# Project_datacommunicatie.net
KiCad netlist of a schematic drawn in EAGLE
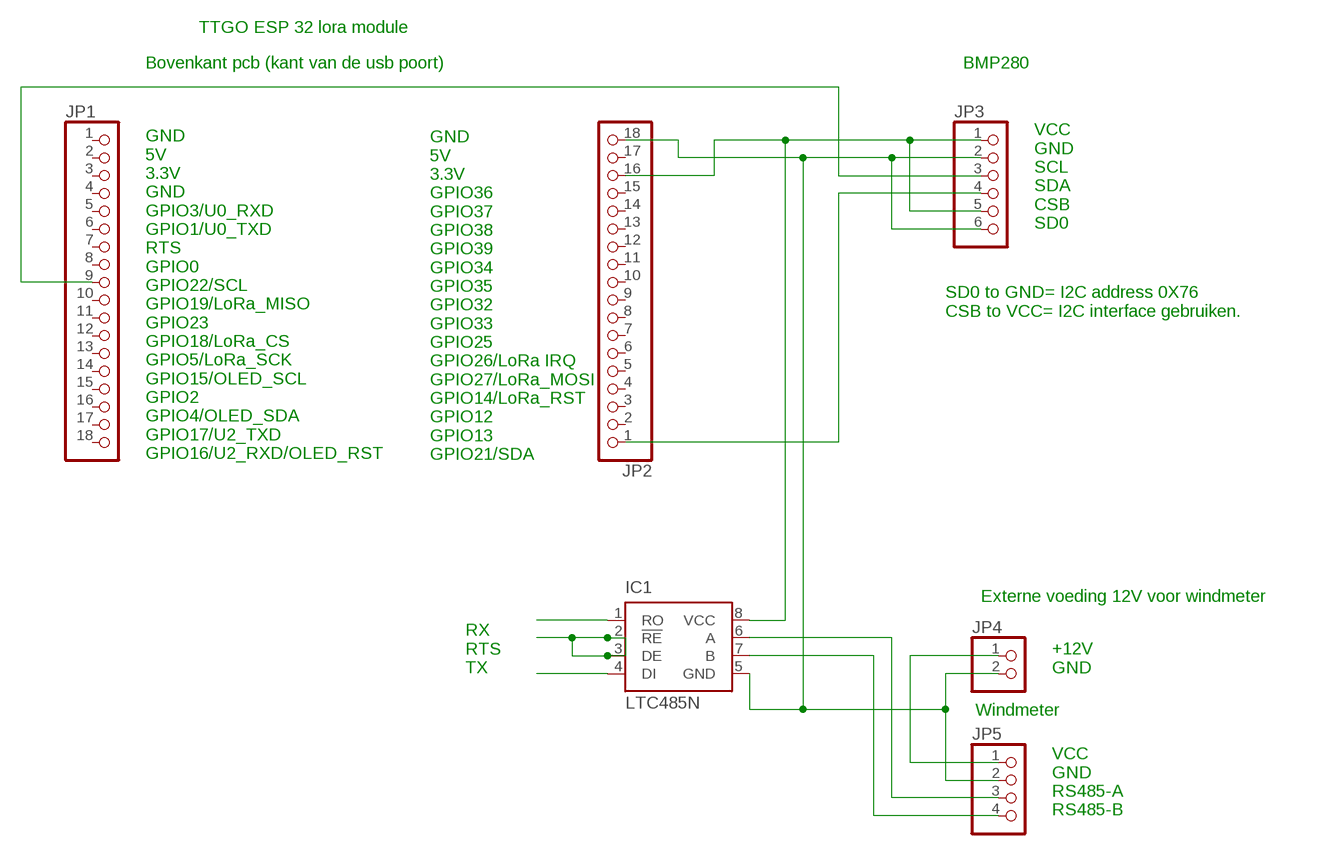
[diagram p0: schematic, sheet 1]

(export (version "E")
  (design (tool "Eeschema 10.0.6"))
  (components
    (comp (ref "IC1")
      (value "LTC485N")
      (footprint "eagle-import:DIL08")
      (libsource (lib "eagle-import") (part "LTC485N"))
    )
    (comp (ref "JP1")
      (value "PINHD-1X18")
      (footprint "eagle-import:1X18")
      (libsource (lib "eagle-import") (part "PINHD-1X18"))
    )
    (comp (ref "JP2")
      (value "PINHD-1X18")
      (footprint "eagle-import:1X18")
      (libsource (lib "eagle-import") (part "PINHD-1X18"))
    )
    (comp (ref "JP3")
      (value "PINHD-1X6")
      (footprint "eagle-import:1X06")
      (libsource (lib "eagle-import") (part "PINHD-1X6"))
    )
    (comp (ref "JP4")
      (value "PINHD-1X2")
      (footprint "eagle-import:1X02")
      (libsource (lib "eagle-import") (part "PINHD-1X2"))
    )
    (comp (ref "JP5")
      (value "PINHD-1X4")
      (footprint "eagle-import:1X04")
      (libsource (lib "eagle-import") (part "PINHD-1X4"))
    )
  )
  (nets
    (net (code "1") (name "Net-(IC1-A)") (class "Default")
      (node (ref "IC1") (pin "6") (pinfunction "A_6") (pintype "bidirectional"))
      (node (ref "JP5") (pin "3") (pinfunction "3_3") (pintype "passive"))
    )
    (net (code "2") (name "Net-(IC1-B)") (class "Default")
      (node (ref "IC1") (pin "7") (pinfunction "B_7") (pintype "bidirectional"))
      (node (ref "JP5") (pin "4") (pinfunction "4_4") (pintype "passive"))
    )
    (net (code "3") (name "Net-(IC1-DE)") (class "Default")
      (node (ref "IC1") (pin "2") (pinfunction "~{RE}_2") (pintype "input"))
      (node (ref "IC1") (pin "3") (pinfunction "DE_3") (pintype "input"))
    )
    (net (code "4") (name "Net-(IC1-GND)") (class "Default")
      (node (ref "IC1") (pin "5") (pinfunction "GND_5") (pintype "input"))
      (node (ref "JP2") (pin "18") (pinfunction "18_18") (pintype "passive"))
      (node (ref "JP3") (pin "2") (pinfunction "2_2") (pintype "passive"))
      (node (ref "JP3") (pin "6") (pinfunction "6_6") (pintype "passive"))
      (node (ref "JP4") (pin "2") (pinfunction "2_2") (pintype "passive"))
      (node (ref "JP5") (pin "2") (pinfunction "2_2") (pintype "passive"))
    )
    (net (code "5") (name "Net-(IC1-VCC)") (class "Default")
      (node (ref "IC1") (pin "8") (pinfunction "VCC_8") (pintype "input"))
      (node (ref "JP2") (pin "16") (pinfunction "16_16") (pintype "passive"))
      (node (ref "JP3") (pin "1") (pinfunction "1_1") (pintype "passive"))
      (node (ref "JP3") (pin "5") (pinfunction "5_5") (pintype "passive"))
    )
    (net (code "6") (name "Net-(JP1-Pad9)") (class "Default")
      (node (ref "JP1") (pin "9") (pinfunction "9_9") (pintype "passive"))
      (node (ref "JP3") (pin "3") (pinfunction "3_3") (pintype "passive"))
    )
    (net (code "7") (name "Net-(JP2-Pad1)") (class "Default")
      (node (ref "JP2") (pin "1") (pinfunction "1_1") (pintype "passive"))
      (node (ref "JP3") (pin "4") (pinfunction "4_4") (pintype "passive"))
    )
    (net (code "8") (name "Net-(JP4-Pad1)") (class "Default")
      (node (ref "JP4") (pin "1") (pinfunction "1_1") (pintype "passive"))
      (node (ref "JP5") (pin "1") (pinfunction "1_1") (pintype "passive"))
    )
    (net (code "9") (name "unconnected-(IC1-DI-Pad4)") (class "Default")
      (node (ref "IC1") (pin "4") (pinfunction "DI_4") (pintype "input"))
    )
    (net (code "10") (name "unconnected-(IC1-RO-Pad1)") (class "Default")
      (node (ref "IC1") (pin "1") (pinfunction "RO_1") (pintype "output"))
    )
    (net (code "11") (name "unconnected-(JP1-Pad1)") (class "Default")
      (node (ref "JP1") (pin "1") (pinfunction "1_1") (pintype "passive"))
    )
    (net (code "12") (name "unconnected-(JP1-Pad2)") (class "Default")
      (node (ref "JP1") (pin "2") (pinfunction "2_2") (pintype "passive"))
    )
    (net (code "13") (name "unconnected-(JP1-Pad3)") (class "Default")
      (node (ref "JP1") (pin "3") (pinfunction "3_3") (pintype "passive"))
    )
    (net (code "14") (name "unconnected-(JP1-Pad4)") (class "Default")
      (node (ref "JP1") (pin "4") (pinfunction "4_4") (pintype "passive"))
    )
    (net (code "15") (name "unconnected-(JP1-Pad5)") (class "Default")
      (node (ref "JP1") (pin "5") (pinfunction "5_5") (pintype "passive"))
    )
    (net (code "16") (name "unconnected-(JP1-Pad6)") (class "Default")
      (node (ref "JP1") (pin "6") (pinfunction "6_6") (pintype "passive"))
    )
    (net (code "17") (name "unconnected-(JP1-Pad7)") (class "Default")
      (node (ref "JP1") (pin "7") (pinfunction "7_7") (pintype "passive"))
    )
    (net (code "18") (name "unconnected-(JP1-Pad8)") (class "Default")
      (node (ref "JP1") (pin "8") (pinfunction "8_8") (pintype "passive"))
    )
    (net (code "19") (name "unconnected-(JP1-Pad10)") (class "Default")
      (node (ref "JP1") (pin "10") (pinfunction "10_10") (pintype "passive"))
    )
    (net (code "20") (name "unconnected-(JP1-Pad11)") (class "Default")
      (node (ref "JP1") (pin "11") (pinfunction "11_11") (pintype "passive"))
    )
    (net (code "21") (name "unconnected-(JP1-Pad12)") (class "Default")
      (node (ref "JP1") (pin "12") (pinfunction "12_12") (pintype "passive"))
    )
    (net (code "22") (name "unconnected-(JP1-Pad13)") (class "Default")
      (node (ref "JP1") (pin "13") (pinfunction "13_13") (pintype "passive"))
    )
    (net (code "23") (name "unconnected-(JP1-Pad14)") (class "Default")
      (node (ref "JP1") (pin "14") (pinfunction "14_14") (pintype "passive"))
    )
    (net (code "24") (name "unconnected-(JP1-Pad15)") (class "Default")
      (node (ref "JP1") (pin "15") (pinfunction "15_15") (pintype "passive"))
    )
    (net (code "25") (name "unconnected-(JP1-Pad16)") (class "Default")
      (node (ref "JP1") (pin "16") (pinfunction "16_16") (pintype "passive"))
    )
    (net (code "26") (name "unconnected-(JP1-Pad17)") (class "Default")
      (node (ref "JP1") (pin "17") (pinfunction "17_17") (pintype "passive"))
    )
    (net (code "27") (name "unconnected-(JP1-Pad18)") (class "Default")
      (node (ref "JP1") (pin "18") (pinfunction "18_18") (pintype "passive"))
    )
    (net (code "28") (name "unconnected-(JP2-Pad2)") (class "Default")
      (node (ref "JP2") (pin "2") (pinfunction "2_2") (pintype "passive"))
    )
    (net (code "29") (name "unconnected-(JP2-Pad3)") (class "Default")
      (node (ref "JP2") (pin "3") (pinfunction "3_3") (pintype "passive"))
    )
    (net (code "30") (name "unconnected-(JP2-Pad4)") (class "Default")
      (node (ref "JP2") (pin "4") (pinfunction "4_4") (pintype "passive"))
    )
    (net (code "31") (name "unconnected-(JP2-Pad5)") (class "Default")
      (node (ref "JP2") (pin "5") (pinfunction "5_5") (pintype "passive"))
    )
    (net (code "32") (name "unconnected-(JP2-Pad6)") (class "Default")
      (node (ref "JP2") (pin "6") (pinfunction "6_6") (pintype "passive"))
    )
    (net (code "33") (name "unconnected-(JP2-Pad7)") (class "Default")
      (node (ref "JP2") (pin "7") (pinfunction "7_7") (pintype "passive"))
    )
    (net (code "34") (name "unconnected-(JP2-Pad8)") (class "Default")
      (node (ref "JP2") (pin "8") (pinfunction "8_8") (pintype "passive"))
    )
    (net (code "35") (name "unconnected-(JP2-Pad9)") (class "Default")
      (node (ref "JP2") (pin "9") (pinfunction "9_9") (pintype "passive"))
    )
    (net (code "36") (name "unconnected-(JP2-Pad10)") (class "Default")
      (node (ref "JP2") (pin "10") (pinfunction "10_10") (pintype "passive"))
    )
    (net (code "37") (name "unconnected-(JP2-Pad11)") (class "Default")
      (node (ref "JP2") (pin "11") (pinfunction "11_11") (pintype "passive"))
    )
    (net (code "38") (name "unconnected-(JP2-Pad12)") (class "Default")
      (node (ref "JP2") (pin "12") (pinfunction "12_12") (pintype "passive"))
    )
    (net (code "39") (name "unconnected-(JP2-Pad13)") (class "Default")
      (node (ref "JP2") (pin "13") (pinfunction "13_13") (pintype "passive"))
    )
    (net (code "40") (name "unconnected-(JP2-Pad14)") (class "Default")
      (node (ref "JP2") (pin "14") (pinfunction "14_14") (pintype "passive"))
    )
    (net (code "41") (name "unconnected-(JP2-Pad15)") (class "Default")
      (node (ref "JP2") (pin "15") (pinfunction "15_15") (pintype "passive"))
    )
    (net (code "42") (name "unconnected-(JP2-Pad17)") (class "Default")
      (node (ref "JP2") (pin "17") (pinfunction "17_17") (pintype "passive"))
    )
  )
)
